# Audio_receiver.net
KiCad netlist of a schematic drawn in Altium Designer
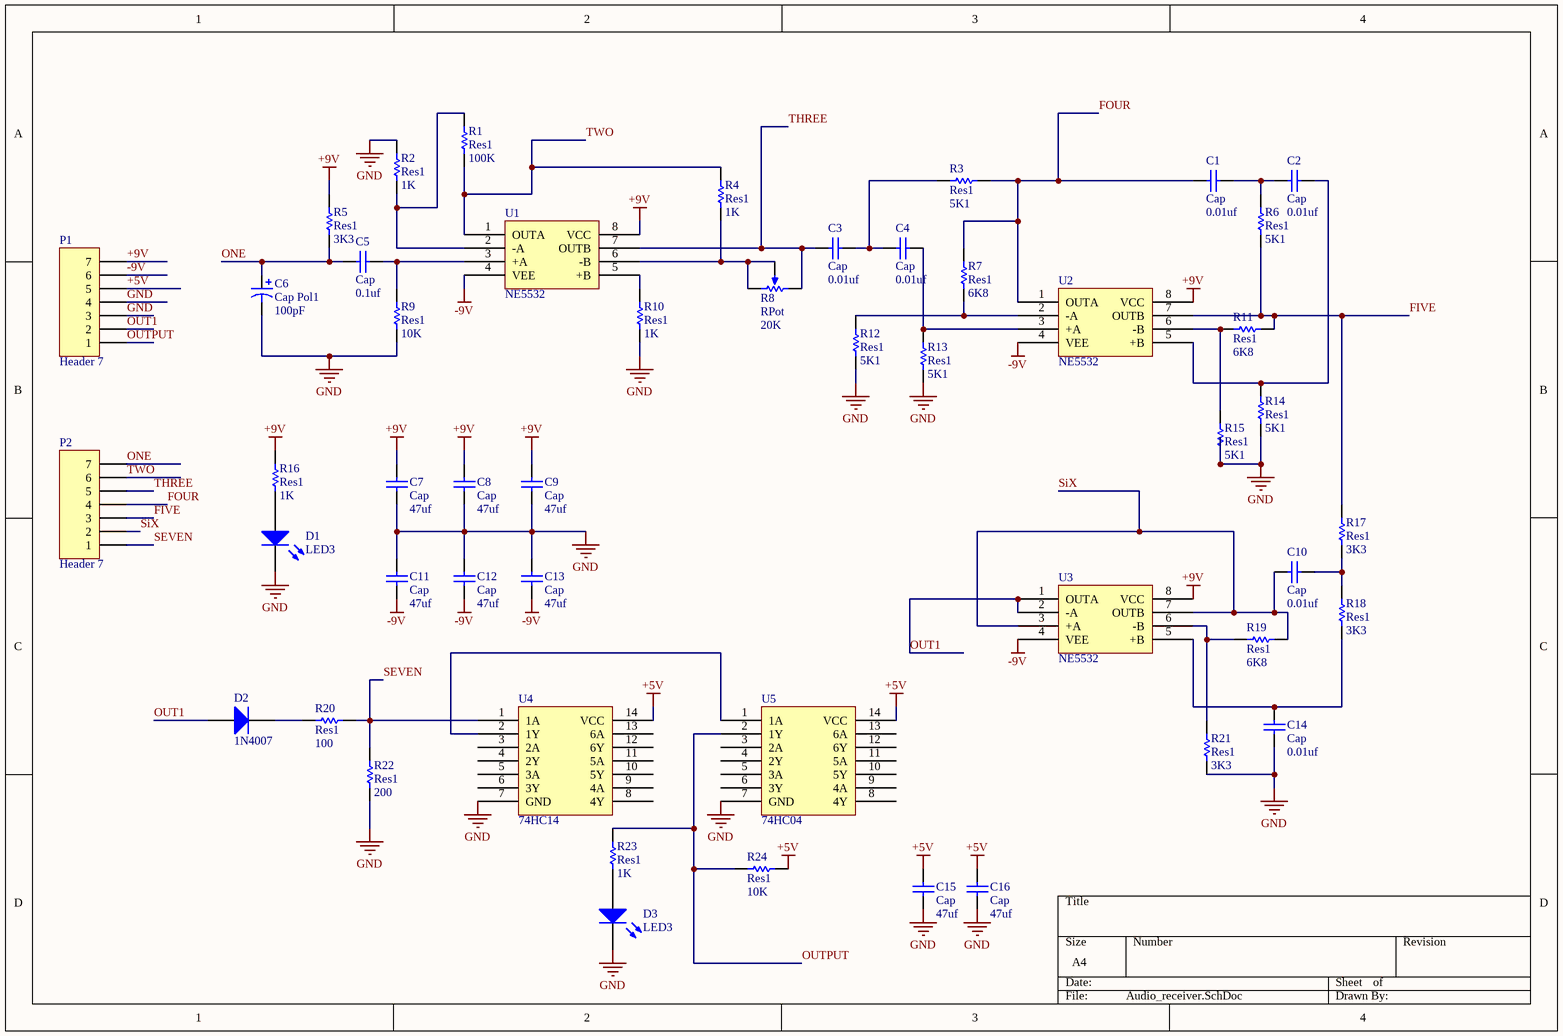
[diagram p0: Audio_receiver.SchDoc]

(export (version "E")
  (design (tool "Eeschema 10.0.6"))
  (components
    (comp (ref "C1")
      (value "Cap")
      (footprint "C0805")
      (description "Capacitor")
      (fields (field (name "ALTIUM_VALUE") "0.01uf") (field (name "PUBLISHER") "Altium Limited"))
      (libsource (lib "Miscellaneous Devices") (part "Cap"))
    )
    (comp (ref "C2")
      (value "Cap")
      (footprint "C0805")
      (description "Capacitor")
      (fields (field (name "ALTIUM_VALUE") "0.01uf") (field (name "PUBLISHER") "Altium Limited"))
      (libsource (lib "Miscellaneous Devices") (part "Cap"))
    )
    (comp (ref "C3")
      (value "Cap")
      (footprint "C0805")
      (description "Capacitor")
      (fields (field (name "ALTIUM_VALUE") "0.01uf") (field (name "PUBLISHER") "Altium Limited"))
      (libsource (lib "Miscellaneous Devices") (part "Cap"))
    )
    (comp (ref "C4")
      (value "Cap")
      (footprint "C0805")
      (description "Capacitor")
      (fields (field (name "ALTIUM_VALUE") "0.01uf") (field (name "PUBLISHER") "Altium Limited"))
      (libsource (lib "Miscellaneous Devices") (part "Cap"))
    )
    (comp (ref "C5")
      (value "Cap")
      (footprint "C0805")
      (description "Capacitor")
      (fields (field (name "ALTIUM_VALUE") "0.1uf") (field (name "PUBLISHER") "Altium Limited"))
      (libsource (lib "Miscellaneous Devices") (part "Cap"))
    )
    (comp (ref "C6")
      (value "Cap Pol1")
      (footprint "CAPR5-4X5")
      (description "Polarized Capacitor (Radial)")
      (fields (field (name "ALTIUM_VALUE") "100pF") (field (name "PUBLISHER") "Altium Limited"))
      (libsource (lib "Miscellaneous Devices") (part "Cap Pol1"))
    )
    (comp (ref "C7")
      (value "Cap")
      (footprint "CAPR5-4X5")
      (description "Capacitor")
      (fields (field (name "ALTIUM_VALUE") "47uf") (field (name "PUBLISHER") "Altium Limited"))
      (libsource (lib "Miscellaneous Devices") (part "Cap"))
    )
    (comp (ref "C8")
      (value "Cap")
      (footprint "CAPR5-4X5")
      (description "Capacitor")
      (fields (field (name "ALTIUM_VALUE") "47uf") (field (name "PUBLISHER") "Altium Limited"))
      (libsource (lib "Miscellaneous Devices") (part "Cap"))
    )
    (comp (ref "C9")
      (value "Cap")
      (footprint "CAPR5-4X5")
      (description "Capacitor")
      (fields (field (name "ALTIUM_VALUE") "47uf") (field (name "PUBLISHER") "Altium Limited"))
      (libsource (lib "Miscellaneous Devices") (part "Cap"))
    )
    (comp (ref "C10")
      (value "Cap")
      (footprint "C0805")
      (description "Capacitor")
      (fields (field (name "ALTIUM_VALUE") "0.01uf") (field (name "PUBLISHER") "Altium Limited"))
      (libsource (lib "Miscellaneous Devices") (part "Cap"))
    )
    (comp (ref "C11")
      (value "Cap")
      (footprint "CAPR5-4X5")
      (description "Capacitor")
      (fields (field (name "ALTIUM_VALUE") "47uf") (field (name "PUBLISHER") "Altium Limited"))
      (libsource (lib "Miscellaneous Devices") (part "Cap"))
    )
    (comp (ref "C12")
      (value "Cap")
      (footprint "CAPR5-4X5")
      (description "Capacitor")
      (fields (field (name "ALTIUM_VALUE") "47uf") (field (name "PUBLISHER") "Altium Limited"))
      (libsource (lib "Miscellaneous Devices") (part "Cap"))
    )
    (comp (ref "C13")
      (value "Cap")
      (footprint "CAPR5-4X5")
      (description "Capacitor")
      (fields (field (name "ALTIUM_VALUE") "47uf") (field (name "PUBLISHER") "Altium Limited"))
      (libsource (lib "Miscellaneous Devices") (part "Cap"))
    )
    (comp (ref "C14")
      (value "Cap")
      (footprint "C0805")
      (description "Capacitor")
      (fields (field (name "ALTIUM_VALUE") "0.01uf") (field (name "PUBLISHER") "Altium Limited"))
      (libsource (lib "Miscellaneous Devices") (part "Cap"))
    )
    (comp (ref "C15")
      (value "Cap")
      (footprint "CAPR5-4X5")
      (description "Capacitor")
      (fields (field (name "ALTIUM_VALUE") "47uf") (field (name "PUBLISHER") "Altium Limited"))
      (libsource (lib "Miscellaneous Devices") (part "Cap"))
    )
    (comp (ref "C16")
      (value "Cap")
      (footprint "CAPR5-4X5")
      (description "Capacitor")
      (fields (field (name "ALTIUM_VALUE") "47uf") (field (name "PUBLISHER") "Altium Limited"))
      (libsource (lib "Miscellaneous Devices") (part "Cap"))
    )
    (comp (ref "D1")
      (value "LED3")
      (footprint "3.5X2.8X1.9")
      (description "Typical BLUE SiC LED")
      (fields (field (name "PUBLISHER") "Altium Limited"))
      (libsource (lib "Miscellaneous Devices") (part "LED3"))
    )
    (comp (ref "D2")
      (value "1N4007")
      (footprint "DO-35A")
      (description "Default Diode")
      (fields (field (name "PUBLISHER") "Altium Limited"))
      (libsource (lib "Miscellaneous Devices") (part "Diode"))
    )
    (comp (ref "D3")
      (value "LED3")
      (footprint "3.5X2.8X1.9")
      (description "Typical BLUE SiC LED")
      (fields (field (name "PUBLISHER") "Altium Limited"))
      (libsource (lib "Miscellaneous Devices") (part "LED3"))
    )
    (comp (ref "P1")
      (value "Header 7")
      (footprint "HDR1X7")
      (description "Header, 7-Pin")
      (fields (field (name "PUBLISHER") "Altium Limited"))
      (libsource (lib "Miscellaneous Connectors") (part "Header 7"))
    )
    (comp (ref "P2")
      (value "Header 7")
      (footprint "HDR1X7")
      (description "Header, 7-Pin")
      (fields (field (name "PUBLISHER") "Altium Limited"))
      (libsource (lib "Miscellaneous Connectors") (part "Header 7"))
    )
    (comp (ref "R1")
      (value "Res1")
      (footprint "6-0805_L")
      (description "Resistor")
      (fields (field (name "ALTIUM_VALUE") "100K") (field (name "PUBLISHER") "Altium Limited"))
      (libsource (lib "Miscellaneous Devices") (part "Res1"))
    )
    (comp (ref "R2")
      (value "Res1")
      (footprint "6-0805_L")
      (description "Resistor")
      (fields (field (name "ALTIUM_VALUE") "1K") (field (name "PUBLISHER") "Altium Limited"))
      (libsource (lib "Miscellaneous Devices") (part "Res1"))
    )
    (comp (ref "R3")
      (value "Res1")
      (footprint "6-0805_L")
      (description "Resistor")
      (fields (field (name "ALTIUM_VALUE") "5K1") (field (name "PUBLISHER") "Altium Limited"))
      (libsource (lib "Miscellaneous Devices") (part "Res1"))
    )
    (comp (ref "R4")
      (value "Res1")
      (footprint "6-0805_L")
      (description "Resistor")
      (fields (field (name "ALTIUM_VALUE") "1K") (field (name "PUBLISHER") "Altium Limited"))
      (libsource (lib "Miscellaneous Devices") (part "Res1"))
    )
    (comp (ref "R5")
      (value "Res1")
      (footprint "6-0805_L")
      (description "Resistor")
      (fields (field (name "ALTIUM_VALUE") "3K3") (field (name "PUBLISHER") "Altium Limited"))
      (libsource (lib "Miscellaneous Devices") (part "Res1"))
    )
    (comp (ref "R6")
      (value "Res1")
      (footprint "6-0805_L")
      (description "Resistor")
      (fields (field (name "ALTIUM_VALUE") "5K1") (field (name "PUBLISHER") "Altium Limited"))
      (libsource (lib "Miscellaneous Devices") (part "Res1"))
    )
    (comp (ref "R7")
      (value "Res1")
      (footprint "6-0805_L")
      (description "Resistor")
      (fields (field (name "ALTIUM_VALUE") "6K8") (field (name "PUBLISHER") "Altium Limited"))
      (libsource (lib "Miscellaneous Devices") (part "Res1"))
    )
    (comp (ref "R8")
      (value "RPot")
      (footprint "VR5")
      (description "Potentiometer")
      (fields (field (name "ALTIUM_VALUE") "20K") (field (name "PUBLISHER") "Altium Limited"))
      (libsource (lib "Miscellaneous Devices") (part "RPot"))
    )
    (comp (ref "R9")
      (value "Res1")
      (footprint "6-0805_L")
      (description "Resistor")
      (fields (field (name "ALTIUM_VALUE") "10K") (field (name "PUBLISHER") "Altium Limited"))
      (libsource (lib "Miscellaneous Devices") (part "Res1"))
    )
    (comp (ref "R10")
      (value "Res1")
      (footprint "6-0805_L")
      (description "Resistor")
      (fields (field (name "ALTIUM_VALUE") "1K") (field (name "PUBLISHER") "Altium Limited"))
      (libsource (lib "Miscellaneous Devices") (part "Res1"))
    )
    (comp (ref "R11")
      (value "Res1")
      (footprint "6-0805_L")
      (description "Resistor")
      (fields (field (name "ALTIUM_VALUE") "6K8") (field (name "PUBLISHER") "Altium Limited"))
      (libsource (lib "Miscellaneous Devices") (part "Res1"))
    )
    (comp (ref "R12")
      (value "Res1")
      (footprint "6-0805_L")
      (description "Resistor")
      (fields (field (name "ALTIUM_VALUE") "5K1") (field (name "PUBLISHER") "Altium Limited"))
      (libsource (lib "Miscellaneous Devices") (part "Res1"))
    )
    (comp (ref "R13")
      (value "Res1")
      (footprint "6-0805_L")
      (description "Resistor")
      (fields (field (name "ALTIUM_VALUE") "5K1") (field (name "PUBLISHER") "Altium Limited"))
      (libsource (lib "Miscellaneous Devices") (part "Res1"))
    )
    (comp (ref "R14")
      (value "Res1")
      (footprint "6-0805_L")
      (description "Resistor")
      (fields (field (name "ALTIUM_VALUE") "5K1") (field (name "PUBLISHER") "Altium Limited"))
      (libsource (lib "Miscellaneous Devices") (part "Res1"))
    )
    (comp (ref "R15")
      (value "Res1")
      (footprint "6-0805_L")
      (description "Resistor")
      (fields (field (name "ALTIUM_VALUE") "5K1") (field (name "PUBLISHER") "Altium Limited"))
      (libsource (lib "Miscellaneous Devices") (part "Res1"))
    )
    (comp (ref "R16")
      (value "Res1")
      (footprint "6-0805_N")
      (description "Resistor")
      (fields (field (name "ALTIUM_VALUE") "1K") (field (name "PUBLISHER") "Altium Limited"))
      (libsource (lib "Miscellaneous Devices") (part "Res1"))
    )
    (comp (ref "R17")
      (value "Res1")
      (footprint "6-0805_L")
      (description "Resistor")
      (fields (field (name "ALTIUM_VALUE") "3K3") (field (name "PUBLISHER") "Altium Limited"))
      (libsource (lib "Miscellaneous Devices") (part "Res1"))
    )
    (comp (ref "R18")
      (value "Res1")
      (footprint "6-0805_L")
      (description "Resistor")
      (fields (field (name "ALTIUM_VALUE") "3K3") (field (name "PUBLISHER") "Altium Limited"))
      (libsource (lib "Miscellaneous Devices") (part "Res1"))
    )
    (comp (ref "R19")
      (value "Res1")
      (footprint "6-0805_L")
      (description "Resistor")
      (fields (field (name "ALTIUM_VALUE") "6K8") (field (name "PUBLISHER") "Altium Limited"))
      (libsource (lib "Miscellaneous Devices") (part "Res1"))
    )
    (comp (ref "R20")
      (value "Res1")
      (footprint "6-0805_L")
      (description "Resistor")
      (fields (field (name "ALTIUM_VALUE") "100") (field (name "PUBLISHER") "Altium Limited"))
      (libsource (lib "Miscellaneous Devices") (part "Res1"))
    )
    (comp (ref "R21")
      (value "Res1")
      (footprint "6-0805_L")
      (description "Resistor")
      (fields (field (name "ALTIUM_VALUE") "3K3") (field (name "PUBLISHER") "Altium Limited"))
      (libsource (lib "Miscellaneous Devices") (part "Res1"))
    )
    (comp (ref "R22")
      (value "Res1")
      (footprint "6-0805_L")
      (description "Resistor")
      (fields (field (name "ALTIUM_VALUE") "200") (field (name "PUBLISHER") "Altium Limited"))
      (libsource (lib "Miscellaneous Devices") (part "Res1"))
    )
    (comp (ref "R23")
      (value "Res1")
      (footprint "6-0805_L")
      (description "Resistor")
      (fields (field (name "ALTIUM_VALUE") "1K") (field (name "PUBLISHER") "Altium Limited"))
      (libsource (lib "Miscellaneous Devices") (part "Res1"))
    )
    (comp (ref "R24")
      (value "Res1")
      (footprint "6-0805_L")
      (description "Resistor")
      (fields (field (name "ALTIUM_VALUE") "10K") (field (name "PUBLISHER") "Altium Limited"))
      (libsource (lib "Miscellaneous Devices") (part "Res1"))
    )
    (comp (ref "U1") (value "NE5532") (footprint "DIP-8") (libsource (lib "NE5532") (part "NE5532")))
    (comp (ref "U2") (value "NE5532") (footprint "DIP-8") (libsource (lib "NE5532") (part "NE5532")))
    (comp (ref "U3") (value "NE5532") (footprint "DIP-8") (libsource (lib "NE5532") (part "NE5532")))
    (comp (ref "U4") (value "74HC14") (footprint "DIP-14") (libsource (lib "NE5532") (part "74HC14")))
    (comp (ref "U5") (value "74HC04") (footprint "DIP-14") (libsource (lib "NE5532") (part "74HC04")))
  )
  (nets
    (net (code "1") (name "+5V") (class "Default")
      (node (ref "C15") (pin "2") (pinfunction "2_2") (pintype "passive"))
      (node (ref "C16") (pin "2") (pinfunction "2_2") (pintype "passive"))
      (node (ref "P1") (pin "5") (pinfunction "5_5") (pintype "passive"))
      (node (ref "R24") (pin "1") (pinfunction "1_1") (pintype "passive"))
      (node (ref "U4") (pin "14") (pinfunction "VCC_14") (pintype "passive"))
      (node (ref "U5") (pin "14") (pinfunction "VCC_14") (pintype "passive"))
    )
    (net (code "2") (name "+9V") (class "Default")
      (node (ref "C7") (pin "2") (pinfunction "2_2") (pintype "passive"))
      (node (ref "C8") (pin "2") (pinfunction "2_2") (pintype "passive"))
      (node (ref "C9") (pin "2") (pinfunction "2_2") (pintype "passive"))
      (node (ref "P1") (pin "7") (pinfunction "7_7") (pintype "passive"))
      (node (ref "R16") (pin "2") (pinfunction "2_2") (pintype "passive"))
      (node (ref "R5") (pin "2") (pinfunction "2_2") (pintype "passive"))
      (node (ref "U1") (pin "8") (pinfunction "VCC_8") (pintype "passive"))
      (node (ref "U2") (pin "8") (pinfunction "VCC_8") (pintype "passive"))
      (node (ref "U3") (pin "8") (pinfunction "VCC_8") (pintype "passive"))
    )
    (net (code "3") (name "-9V") (class "Default")
      (node (ref "C11") (pin "1") (pinfunction "1_1") (pintype "passive"))
      (node (ref "C12") (pin "1") (pinfunction "1_1") (pintype "passive"))
      (node (ref "C13") (pin "1") (pinfunction "1_1") (pintype "passive"))
      (node (ref "P1") (pin "6") (pinfunction "6_6") (pintype "passive"))
      (node (ref "U1") (pin "4") (pinfunction "VEE_4") (pintype "passive"))
      (node (ref "U2") (pin "4") (pinfunction "VEE_4") (pintype "passive"))
      (node (ref "U3") (pin "4") (pinfunction "VEE_4") (pintype "passive"))
    )
    (net (code "4") (name "/FIVE") (class "Default")
      (node (ref "P2") (pin "3") (pinfunction "3_3") (pintype "passive"))
      (node (ref "R11") (pin "2") (pinfunction "2_2") (pintype "passive"))
      (node (ref "R17") (pin "2") (pinfunction "2_2") (pintype "passive"))
      (node (ref "R6") (pin "2") (pinfunction "2_2") (pintype "passive"))
      (node (ref "U2") (pin "7") (pinfunction "OUTB_7") (pintype "passive"))
    )
    (net (code "5") (name "/FOUR") (class "Default")
      (node (ref "C1") (pin "1") (pinfunction "1_1") (pintype "passive"))
      (node (ref "P2") (pin "4") (pinfunction "4_4") (pintype "passive"))
      (node (ref "R3") (pin "1") (pinfunction "1_1") (pintype "passive"))
      (node (ref "R7") (pin "1") (pinfunction "1_1") (pintype "passive"))
      (node (ref "U2") (pin "1") (pinfunction "OUTA_1") (pintype "passive"))
    )
    (net (code "6") (name "/ONE") (class "Default")
      (node (ref "C5") (pin "1") (pinfunction "1_1") (pintype "passive"))
      (node (ref "C6") (pin "1") (pinfunction "1_1") (pintype "passive"))
      (node (ref "P2") (pin "7") (pinfunction "7_7") (pintype "passive"))
      (node (ref "R5") (pin "1") (pinfunction "1_1") (pintype "passive"))
    )
    (net (code "7") (name "/OUT1") (class "Default")
      (node (ref "D2") (pin "1") (pinfunction "A_1") (pintype "passive"))
      (node (ref "P1") (pin "2") (pinfunction "2_2") (pintype "passive"))
      (node (ref "U3") (pin "1") (pinfunction "OUTA_1") (pintype "passive"))
      (node (ref "U3") (pin "2") (pinfunction "-A_2") (pintype "passive"))
    )
    (net (code "8") (name "/OUTPUT") (class "Default")
      (node (ref "P1") (pin "1") (pinfunction "1_1") (pintype "passive"))
      (node (ref "R23") (pin "2") (pinfunction "2_2") (pintype "passive"))
      (node (ref "R24") (pin "2") (pinfunction "2_2") (pintype "passive"))
      (node (ref "U5") (pin "2") (pinfunction "1Y_2") (pintype "passive"))
    )
    (net (code "9") (name "/SEVEN") (class "Default")
      (node (ref "P2") (pin "1") (pinfunction "1_1") (pintype "passive"))
      (node (ref "R20") (pin "1") (pinfunction "1_1") (pintype "passive"))
      (node (ref "R22") (pin "1") (pinfunction "1_1") (pintype "passive"))
      (node (ref "U4") (pin "1") (pinfunction "1A_1") (pintype "passive"))
    )
    (net (code "10") (name "/SiX") (class "Default")
      (node (ref "C10") (pin "2") (pinfunction "2_2") (pintype "passive"))
      (node (ref "P2") (pin "2") (pinfunction "2_2") (pintype "passive"))
      (node (ref "R19") (pin "1") (pinfunction "1_1") (pintype "passive"))
      (node (ref "U3") (pin "3") (pinfunction "+A_3") (pintype "passive"))
      (node (ref "U3") (pin "7") (pinfunction "OUTB_7") (pintype "passive"))
    )
    (net (code "11") (name "/THREE") (class "Default")
      (node (ref "C3") (pin "1") (pinfunction "1_1") (pintype "passive"))
      (node (ref "P2") (pin "5") (pinfunction "5_5") (pintype "passive"))
      (node (ref "R8") (pin "1") (pinfunction "TOP_1") (pintype "passive"))
      (node (ref "U1") (pin "7") (pinfunction "OUTB_7") (pintype "passive"))
    )
    (net (code "12") (name "/TWO") (class "Default")
      (node (ref "P2") (pin "6") (pinfunction "6_6") (pintype "passive"))
      (node (ref "R1") (pin "1") (pinfunction "1_1") (pintype "passive"))
      (node (ref "R4") (pin "2") (pinfunction "2_2") (pintype "passive"))
      (node (ref "U1") (pin "1") (pinfunction "OUTA_1") (pintype "passive"))
    )
    (net (code "13") (name "GND") (class "Default")
      (node (ref "C11") (pin "2") (pinfunction "2_2") (pintype "passive"))
      (node (ref "C12") (pin "2") (pinfunction "2_2") (pintype "passive"))
      (node (ref "C13") (pin "2") (pinfunction "2_2") (pintype "passive"))
      (node (ref "C14") (pin "1") (pinfunction "1_1") (pintype "passive"))
      (node (ref "C15") (pin "1") (pinfunction "1_1") (pintype "passive"))
      (node (ref "C16") (pin "1") (pinfunction "1_1") (pintype "passive"))
      (node (ref "C6") (pin "2") (pinfunction "2_2") (pintype "passive"))
      (node (ref "C7") (pin "1") (pinfunction "1_1") (pintype "passive"))
      (node (ref "C8") (pin "1") (pinfunction "1_1") (pintype "passive"))
      (node (ref "C9") (pin "1") (pinfunction "1_1") (pintype "passive"))
      (node (ref "D1") (pin "2") (pinfunction "K_2") (pintype "passive"))
      (node (ref "D3") (pin "2") (pinfunction "K_2") (pintype "passive"))
      (node (ref "P1") (pin "3") (pinfunction "3_3") (pintype "passive"))
      (node (ref "P1") (pin "4") (pinfunction "4_4") (pintype "passive"))
      (node (ref "R10") (pin "1") (pinfunction "1_1") (pintype "passive"))
      (node (ref "R12") (pin "2") (pinfunction "2_2") (pintype "passive"))
      (node (ref "R13") (pin "2") (pinfunction "2_2") (pintype "passive"))
      (node (ref "R14") (pin "2") (pinfunction "2_2") (pintype "passive"))
      (node (ref "R15") (pin "2") (pinfunction "2_2") (pintype "passive"))
      (node (ref "R2") (pin "2") (pinfunction "2_2") (pintype "passive"))
      (node (ref "R21") (pin "1") (pinfunction "1_1") (pintype "passive"))
      (node (ref "R22") (pin "2") (pinfunction "2_2") (pintype "passive"))
      (node (ref "R9") (pin "1") (pinfunction "1_1") (pintype "passive"))
      (node (ref "U4") (pin "7") (pinfunction "GND_7") (pintype "passive"))
      (node (ref "U5") (pin "7") (pinfunction "GND_7") (pintype "passive"))
    )
    (net (code "14") (name "Net-(C1-Pad2)") (class "Default")
      (node (ref "C1") (pin "2") (pinfunction "2_2") (pintype "passive"))
      (node (ref "C2") (pin "1") (pinfunction "1_1") (pintype "passive"))
      (node (ref "R6") (pin "1") (pinfunction "1_1") (pintype "passive"))
    )
    (net (code "15") (name "Net-(C3-Pad2)") (class "Default")
      (node (ref "C3") (pin "2") (pinfunction "2_2") (pintype "passive"))
      (node (ref "C4") (pin "1") (pinfunction "1_1") (pintype "passive"))
      (node (ref "R3") (pin "2") (pinfunction "2_2") (pintype "passive"))
    )
    (net (code "16") (name "Net-(C10-Pad1)") (class "Default")
      (node (ref "C10") (pin "1") (pinfunction "1_1") (pintype "passive"))
      (node (ref "R17") (pin "1") (pinfunction "1_1") (pintype "passive"))
      (node (ref "R18") (pin "2") (pinfunction "2_2") (pintype "passive"))
    )
    (net (code "17") (name "Net-(D1-A)") (class "Default")
      (node (ref "D1") (pin "1") (pinfunction "A_1") (pintype "passive"))
      (node (ref "R16") (pin "1") (pinfunction "1_1") (pintype "passive"))
    )
    (net (code "18") (name "Net-(D2-K)") (class "Default")
      (node (ref "D2") (pin "2") (pinfunction "K_2") (pintype "passive"))
      (node (ref "R20") (pin "2") (pinfunction "2_2") (pintype "passive"))
    )
    (net (code "19") (name "Net-(D3-A)") (class "Default")
      (node (ref "D3") (pin "1") (pinfunction "A_1") (pintype "passive"))
      (node (ref "R23") (pin "1") (pinfunction "1_1") (pintype "passive"))
    )
    (net (code "20") (name "Net-(R8-BOT)") (class "Default")
      (node (ref "R4") (pin "1") (pinfunction "1_1") (pintype "passive"))
      (node (ref "R8") (pin "2") (pinfunction "BOT_2") (pintype "passive"))
      (node (ref "R8") (pin "3") (pinfunction "TAP_3") (pintype "passive"))
      (node (ref "U1") (pin "6") (pinfunction "-B_6") (pintype "passive"))
    )
    (net (code "21") (name "Net-(U1-+A)") (class "Default")
      (node (ref "C5") (pin "2") (pinfunction "2_2") (pintype "passive"))
      (node (ref "R9") (pin "2") (pinfunction "2_2") (pintype "passive"))
      (node (ref "U1") (pin "3") (pinfunction "+A_3") (pintype "passive"))
    )
    (net (code "22") (name "Net-(U1-+B)") (class "Default")
      (node (ref "R10") (pin "2") (pinfunction "2_2") (pintype "passive"))
      (node (ref "U1") (pin "5") (pinfunction "+B_5") (pintype "passive"))
    )
    (net (code "23") (name "Net-(U1--A)") (class "Default")
      (node (ref "R1") (pin "2") (pinfunction "2_2") (pintype "passive"))
      (node (ref "R2") (pin "1") (pinfunction "1_1") (pintype "passive"))
      (node (ref "U1") (pin "2") (pinfunction "-A_2") (pintype "passive"))
    )
    (net (code "24") (name "Net-(U2-+A)") (class "Default")
      (node (ref "C4") (pin "2") (pinfunction "2_2") (pintype "passive"))
      (node (ref "R13") (pin "1") (pinfunction "1_1") (pintype "passive"))
      (node (ref "U2") (pin "3") (pinfunction "+A_3") (pintype "passive"))
    )
    (net (code "25") (name "Net-(U2-+B)") (class "Default")
      (node (ref "C2") (pin "2") (pinfunction "2_2") (pintype "passive"))
      (node (ref "R14") (pin "1") (pinfunction "1_1") (pintype "passive"))
      (node (ref "U2") (pin "5") (pinfunction "+B_5") (pintype "passive"))
    )
    (net (code "26") (name "Net-(U2--A)") (class "Default")
      (node (ref "R12") (pin "1") (pinfunction "1_1") (pintype "passive"))
      (node (ref "R7") (pin "2") (pinfunction "2_2") (pintype "passive"))
      (node (ref "U2") (pin "2") (pinfunction "-A_2") (pintype "passive"))
    )
    (net (code "27") (name "Net-(U2--B)") (class "Default")
      (node (ref "R11") (pin "1") (pinfunction "1_1") (pintype "passive"))
      (node (ref "R15") (pin "1") (pinfunction "1_1") (pintype "passive"))
      (node (ref "U2") (pin "6") (pinfunction "-B_6") (pintype "passive"))
    )
    (net (code "28") (name "Net-(U3-+B)") (class "Default")
      (node (ref "C14") (pin "2") (pinfunction "2_2") (pintype "passive"))
      (node (ref "R18") (pin "1") (pinfunction "1_1") (pintype "passive"))
      (node (ref "U3") (pin "5") (pinfunction "+B_5") (pintype "passive"))
    )
    (net (code "29") (name "Net-(U3--B)") (class "Default")
      (node (ref "R19") (pin "2") (pinfunction "2_2") (pintype "passive"))
      (node (ref "R21") (pin "2") (pinfunction "2_2") (pintype "passive"))
      (node (ref "U3") (pin "6") (pinfunction "-B_6") (pintype "passive"))
    )
    (net (code "30") (name "Net-(U4-1Y)") (class "Default")
      (node (ref "U4") (pin "2") (pinfunction "1Y_2") (pintype "passive"))
      (node (ref "U5") (pin "1") (pinfunction "1A_1") (pintype "passive"))
    )
    (net (code "31") (name "unconnected-(U4-2A-Pad3)") (class "Default")
      (node (ref "U4") (pin "3") (pinfunction "2A_3") (pintype "passive"))
    )
    (net (code "32") (name "unconnected-(U4-2Y-Pad4)") (class "Default")
      (node (ref "U4") (pin "4") (pinfunction "2Y_4") (pintype "passive"))
    )
    (net (code "33") (name "unconnected-(U4-3A-Pad5)") (class "Default")
      (node (ref "U4") (pin "5") (pinfunction "3A_5") (pintype "passive"))
    )
    (net (code "34") (name "unconnected-(U4-3Y-Pad6)") (class "Default")
      (node (ref "U4") (pin "6") (pinfunction "3Y_6") (pintype "passive"))
    )
    (net (code "35") (name "unconnected-(U4-4A-Pad9)") (class "Default")
      (node (ref "U4") (pin "9") (pinfunction "4A_9") (pintype "passive"))
    )
    (net (code "36") (name "unconnected-(U4-4Y-Pad8)") (class "Default")
      (node (ref "U4") (pin "8") (pinfunction "4Y_8") (pintype "passive"))
    )
    (net (code "37") (name "unconnected-(U4-5A-Pad11)") (class "Default")
      (node (ref "U4") (pin "11") (pinfunction "5A_11") (pintype "passive"))
    )
    (net (code "38") (name "unconnected-(U4-5Y-Pad10)") (class "Default")
      (node (ref "U4") (pin "10") (pinfunction "5Y_10") (pintype "passive"))
    )
    (net (code "39") (name "unconnected-(U4-6A-Pad13)") (class "Default")
      (node (ref "U4") (pin "13") (pinfunction "6A_13") (pintype "passive"))
    )
    (net (code "40") (name "unconnected-(U4-6Y-Pad12)") (class "Default")
      (node (ref "U4") (pin "12") (pinfunction "6Y_12") (pintype "passive"))
    )
    (net (code "41") (name "unconnected-(U5-2A-Pad3)") (class "Default")
      (node (ref "U5") (pin "3") (pinfunction "2A_3") (pintype "passive"))
    )
    (net (code "42") (name "unconnected-(U5-2Y-Pad4)") (class "Default")
      (node (ref "U5") (pin "4") (pinfunction "2Y_4") (pintype "passive"))
    )
    (net (code "43") (name "unconnected-(U5-3A-Pad5)") (class "Default")
      (node (ref "U5") (pin "5") (pinfunction "3A_5") (pintype "passive"))
    )
    (net (code "44") (name "unconnected-(U5-3Y-Pad6)") (class "Default")
      (node (ref "U5") (pin "6") (pinfunction "3Y_6") (pintype "passive"))
    )
    (net (code "45") (name "unconnected-(U5-4A-Pad9)") (class "Default")
      (node (ref "U5") (pin "9") (pinfunction "4A_9") (pintype "passive"))
    )
    (net (code "46") (name "unconnected-(U5-4Y-Pad8)") (class "Default")
      (node (ref "U5") (pin "8") (pinfunction "4Y_8") (pintype "passive"))
    )
    (net (code "47") (name "unconnected-(U5-5A-Pad11)") (class "Default")
      (node (ref "U5") (pin "11") (pinfunction "5A_11") (pintype "passive"))
    )
    (net (code "48") (name "unconnected-(U5-5Y-Pad10)") (class "Default")
      (node (ref "U5") (pin "10") (pinfunction "5Y_10") (pintype "passive"))
    )
    (net (code "49") (name "unconnected-(U5-6A-Pad13)") (class "Default")
      (node (ref "U5") (pin "13") (pinfunction "6A_13") (pintype "passive"))
    )
    (net (code "50") (name "unconnected-(U5-6Y-Pad12)") (class "Default")
      (node (ref "U5") (pin "12") (pinfunction "6Y_12") (pintype "passive"))
    )
  )
)
